# MGB-001-IO-NO-AUDIO.net
KiCad netlist of a schematic drawn in EAGLE
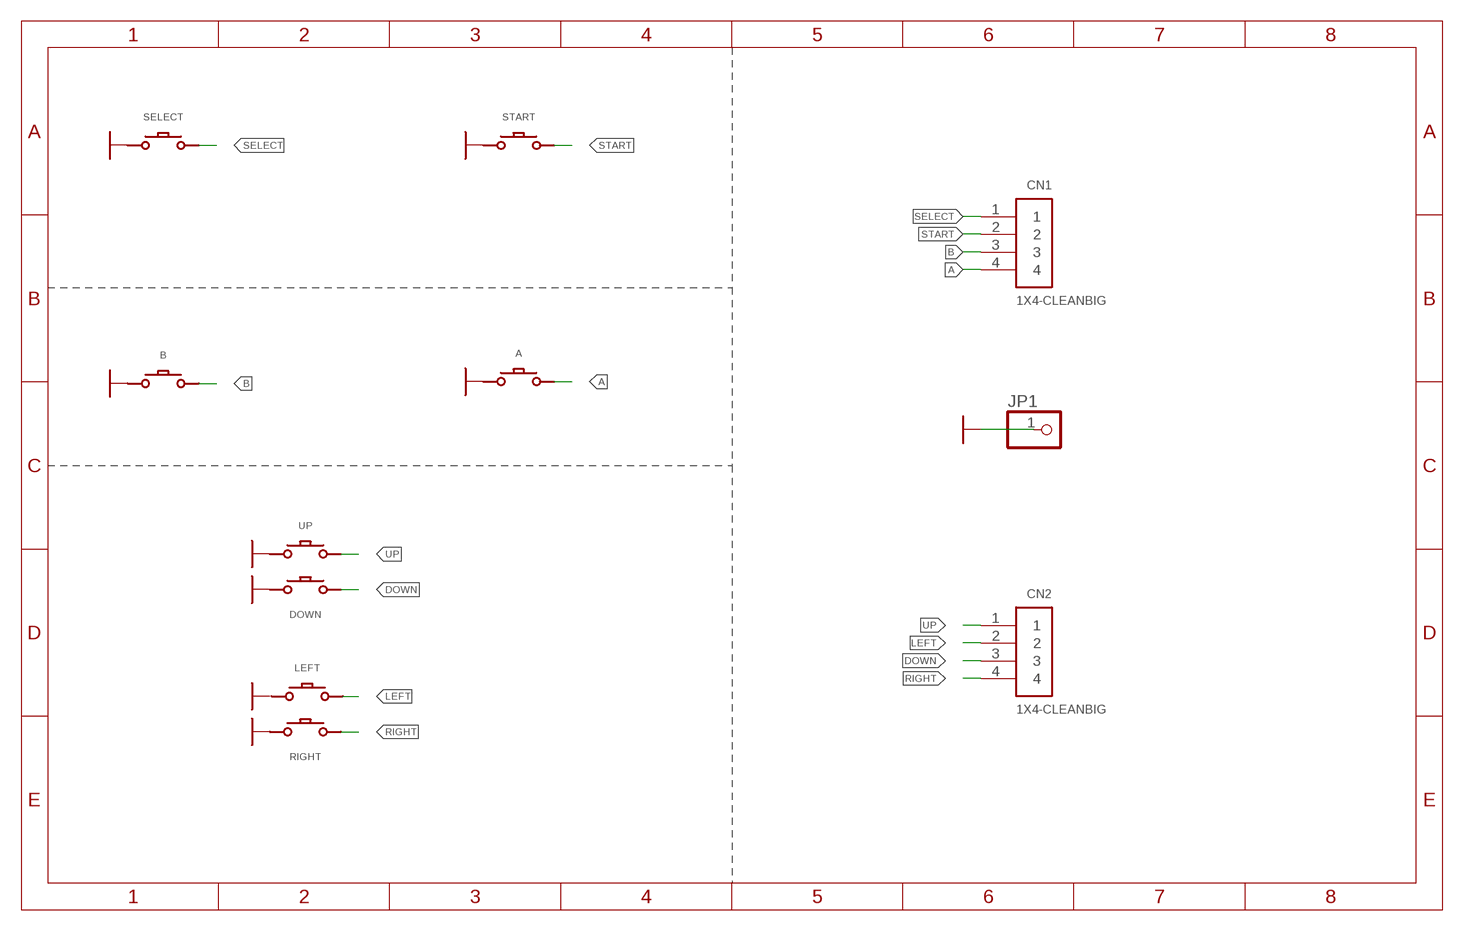
[diagram p0: schematic, sheet 1]
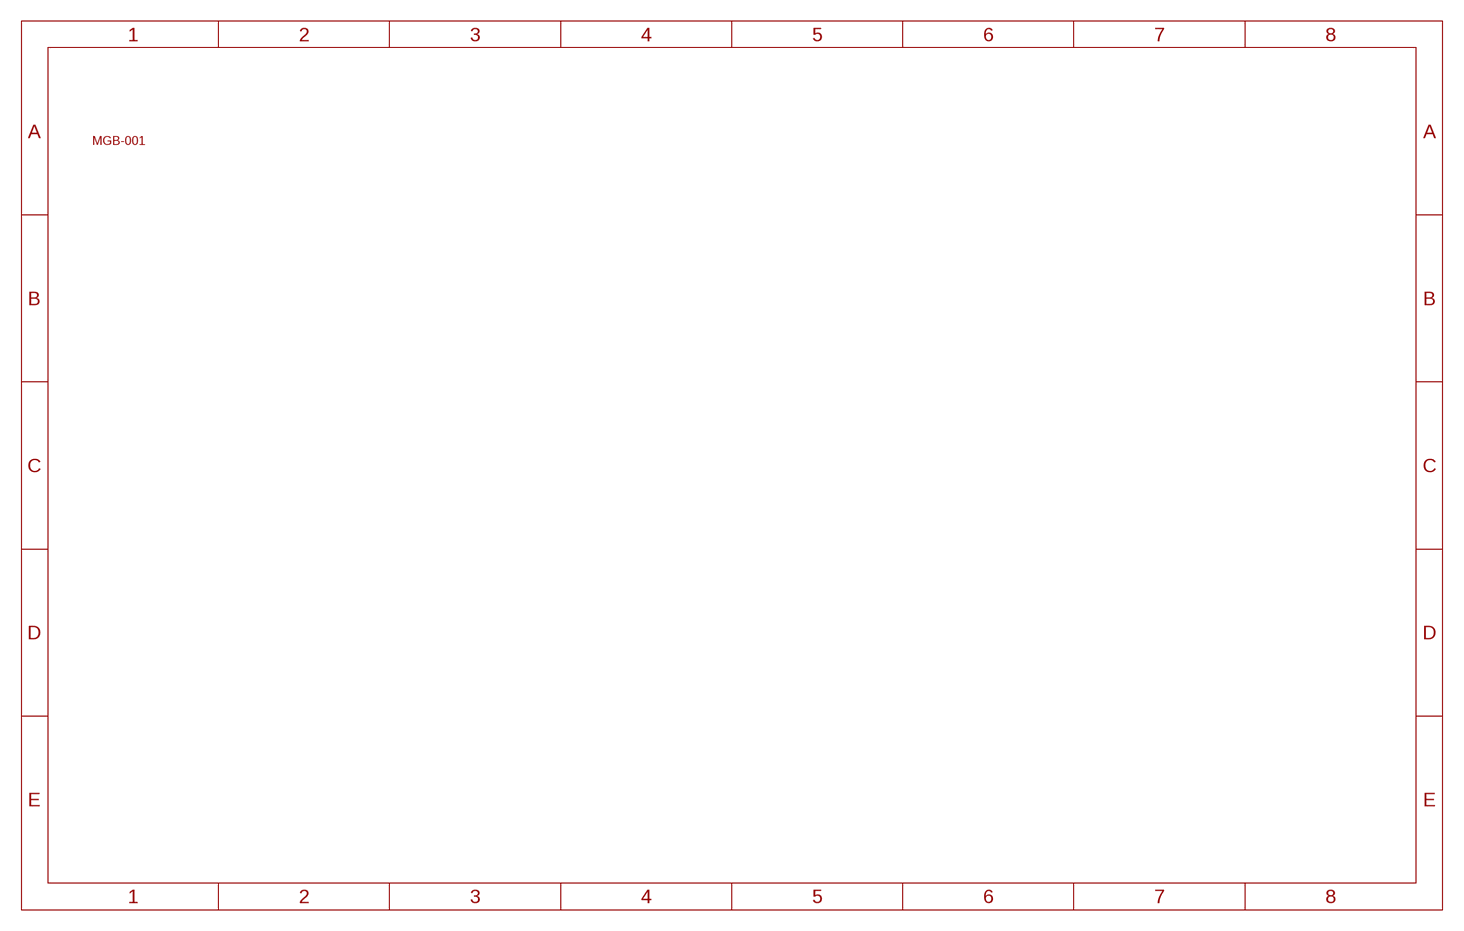
[diagram p1: schematic, sheet 2]

(export (version "E")
  (design (tool "Eeschema 10.0.6"))
  (components
    (comp (ref "U$17")
      (value "MGB-001MGB-001-IO-NO-AUDIO")
      (footprint "eagle-import:MGB-001-IO-NO-AUDIO")
      (libsource (lib "eagle-import") (part "MGB-001MGB-001-IO-NO-AUDIO"))
    )
    (comp (ref "A")
      (value "CONDUCTIVE_BUTTONCONDUCTIVE_BUTTON_THICK")
      (footprint "eagle-import:CONDUCTIVE_BUTTON_THICK")
      (libsource (lib "eagle-import") (part "CONDUCTIVE_BUTTONCONDUCTIVE_BUTTON_THICK"))
    )
    (comp (ref "B")
      (value "CONDUCTIVE_BUTTONCONDUCTIVE_BUTTON_THICK")
      (footprint "eagle-import:CONDUCTIVE_BUTTON_THICK")
      (libsource (lib "eagle-import") (part "CONDUCTIVE_BUTTONCONDUCTIVE_BUTTON_THICK"))
    )
    (comp (ref "CN1")
      (value "1X4-CLEANBIG")
      (footprint "eagle-import:1X04-CLEANBIG")
      (libsource (lib "eagle-import") (part "1X4-CLEANBIG"))
    )
    (comp (ref "CN2")
      (value "1X4-CLEANBIG")
      (footprint "eagle-import:1X04-CLEANBIG")
      (libsource (lib "eagle-import") (part "1X4-CLEANBIG"))
    )
    (comp (ref "DOWN")
      (value "CONDUCTIVE_BUTTONCONDUCTIVE_BUTTON_DIRECTIONAL_THICK")
      (footprint "eagle-import:CONDUCTIVE_BUTTON_DIRECTIONAL_THICK")
      (libsource (lib "eagle-import") (part "CONDUCTIVE_BUTTONCONDUCTIVE_BUTTON_DIRECTIONAL_THICK"))
    )
    (comp (ref "JP1")
      (value "PINHD-1X1CB")
      (footprint "eagle-import:1X01-CLEANBIG")
      (libsource (lib "eagle-import") (part "PINHD-1X1CB"))
    )
    (comp (ref "LEFT")
      (value "CONDUCTIVE_BUTTONCONDUCTIVE_BUTTON_DIRECTIONAL_THICK")
      (footprint "eagle-import:CONDUCTIVE_BUTTON_DIRECTIONAL_THICK")
      (libsource (lib "eagle-import") (part "CONDUCTIVE_BUTTONCONDUCTIVE_BUTTON_DIRECTIONAL_THICK"))
    )
    (comp (ref "RIGHT")
      (value "CONDUCTIVE_BUTTONCONDUCTIVE_BUTTON_DIRECTIONAL_THICK")
      (footprint "eagle-import:CONDUCTIVE_BUTTON_DIRECTIONAL_THICK")
      (libsource (lib "eagle-import") (part "CONDUCTIVE_BUTTONCONDUCTIVE_BUTTON_DIRECTIONAL_THICK"))
    )
    (comp (ref "SELECT")
      (value "CONDUCTIVE_BUTTON_STARTSELECTCONDUCTIVE_BUTTON_THICK_STARTSELECT")
      (footprint "eagle-import:CONDUCTIVE_BUTTON_THICK_STARTSELECT")
      (libsource (lib "eagle-import") (part "CONDUCTIVE_BUTTON_STARTSELECTCONDUCTIVE_BUTTON_THICK_STARTSELECT"))
    )
    (comp (ref "START")
      (value "CONDUCTIVE_BUTTON_STARTSELECTCONDUCTIVE_BUTTON_THICK_STARTSELECT")
      (footprint "eagle-import:CONDUCTIVE_BUTTON_THICK_STARTSELECT")
      (libsource (lib "eagle-import") (part "CONDUCTIVE_BUTTON_STARTSELECTCONDUCTIVE_BUTTON_THICK_STARTSELECT"))
    )
    (comp (ref "UP")
      (value "CONDUCTIVE_BUTTONCONDUCTIVE_BUTTON_DIRECTIONAL_THICK")
      (footprint "eagle-import:CONDUCTIVE_BUTTON_DIRECTIONAL_THICK")
      (libsource (lib "eagle-import") (part "CONDUCTIVE_BUTTONCONDUCTIVE_BUTTON_DIRECTIONAL_THICK"))
    )
  )
  (nets
    (net (code "1") (name "A") (class "Default")
      (node (ref "A") (pin "P$ACTIVE") (pinfunction "P$ACTIVE_P$ACTIVE") (pintype "bidirectional"))
      (node (ref "CN1") (pin "4") (pinfunction "4_4") (pintype "bidirectional"))
    )
    (net (code "2") (name "B") (class "Default")
      (node (ref "B") (pin "P$ACTIVE") (pinfunction "P$ACTIVE_P$ACTIVE") (pintype "bidirectional"))
      (node (ref "CN1") (pin "3") (pinfunction "3_3") (pintype "bidirectional"))
    )
    (net (code "3") (name "DOWN") (class "Default")
      (node (ref "CN2") (pin "3") (pinfunction "3_3") (pintype "bidirectional"))
      (node (ref "DOWN") (pin "P$ACTIVE") (pinfunction "P$ACTIVE_P$ACTIVE") (pintype "bidirectional"))
    )
    (net (code "4") (name "GND") (class "Default")
      (node (ref "A") (pin "P$GND") (pinfunction "P$GND_P$GND") (pintype "bidirectional"))
      (node (ref "B") (pin "P$GND") (pinfunction "P$GND_P$GND") (pintype "bidirectional"))
      (node (ref "DOWN") (pin "P$GND") (pinfunction "P$GND_P$GND") (pintype "bidirectional"))
      (node (ref "JP1") (pin "1") (pinfunction "1_1") (pintype "passive"))
      (node (ref "RIGHT") (pin "P$GND") (pinfunction "P$GND_P$GND") (pintype "bidirectional"))
      (node (ref "SELECT") (pin "P$GND") (pinfunction "P$GND_P$GND") (pintype "bidirectional"))
      (node (ref "SELECT") (pin "P$GND1") (pinfunction "P$GND_P$GND1") (pintype "bidirectional"))
      (node (ref "SELECT") (pin "P$GND2") (pinfunction "P$GND_P$GND2") (pintype "bidirectional"))
      (node (ref "SELECT") (pin "P$GND3") (pinfunction "P$GND_P$GND3") (pintype "bidirectional"))
      (node (ref "START") (pin "P$GND") (pinfunction "P$GND_P$GND") (pintype "bidirectional"))
      (node (ref "START") (pin "P$GND1") (pinfunction "P$GND_P$GND1") (pintype "bidirectional"))
      (node (ref "START") (pin "P$GND2") (pinfunction "P$GND_P$GND2") (pintype "bidirectional"))
      (node (ref "START") (pin "P$GND3") (pinfunction "P$GND_P$GND3") (pintype "bidirectional"))
      (node (ref "UP") (pin "P$GND") (pinfunction "P$GND_P$GND") (pintype "bidirectional"))
    )
    (net (code "5") (name "LEFT") (class "Default")
      (node (ref "CN2") (pin "2") (pinfunction "2_2") (pintype "bidirectional"))
      (node (ref "LEFT") (pin "P$ACTIVE") (pinfunction "P$ACTIVE_P$ACTIVE") (pintype "bidirectional"))
    )
    (net (code "6") (name "RIGHT") (class "Default")
      (node (ref "CN2") (pin "4") (pinfunction "4_4") (pintype "bidirectional"))
      (node (ref "RIGHT") (pin "P$ACTIVE") (pinfunction "P$ACTIVE_P$ACTIVE") (pintype "bidirectional"))
    )
    (net (code "7") (name "SELECT") (class "Default")
      (node (ref "CN1") (pin "1") (pinfunction "1_1") (pintype "bidirectional"))
      (node (ref "SELECT") (pin "P$ACTIVE") (pinfunction "P$ACTIVE_P$ACTIVE") (pintype "bidirectional"))
      (node (ref "SELECT") (pin "P$ACTIVE1") (pinfunction "P$ACTIVE_P$ACTIVE1") (pintype "bidirectional"))
      (node (ref "SELECT") (pin "P$ACTIVE2") (pinfunction "P$ACTIVE_P$ACTIVE2") (pintype "bidirectional"))
      (node (ref "SELECT") (pin "P$ACTIVE3") (pinfunction "P$ACTIVE_P$ACTIVE3") (pintype "bidirectional"))
      (node (ref "SELECT") (pin "P$ACTIVE4") (pinfunction "P$ACTIVE_P$ACTIVE4") (pintype "bidirectional"))
      (node (ref "SELECT") (pin "P$ACTIVE5") (pinfunction "P$ACTIVE_P$ACTIVE5") (pintype "bidirectional"))
      (node (ref "SELECT") (pin "P$ACTIVE6") (pinfunction "P$ACTIVE_P$ACTIVE6") (pintype "bidirectional"))
    )
    (net (code "8") (name "START") (class "Default")
      (node (ref "CN1") (pin "2") (pinfunction "2_2") (pintype "bidirectional"))
      (node (ref "START") (pin "P$ACTIVE") (pinfunction "P$ACTIVE_P$ACTIVE") (pintype "bidirectional"))
      (node (ref "START") (pin "P$ACTIVE1") (pinfunction "P$ACTIVE_P$ACTIVE1") (pintype "bidirectional"))
      (node (ref "START") (pin "P$ACTIVE2") (pinfunction "P$ACTIVE_P$ACTIVE2") (pintype "bidirectional"))
      (node (ref "START") (pin "P$ACTIVE3") (pinfunction "P$ACTIVE_P$ACTIVE3") (pintype "bidirectional"))
      (node (ref "START") (pin "P$ACTIVE4") (pinfunction "P$ACTIVE_P$ACTIVE4") (pintype "bidirectional"))
      (node (ref "START") (pin "P$ACTIVE5") (pinfunction "P$ACTIVE_P$ACTIVE5") (pintype "bidirectional"))
      (node (ref "START") (pin "P$ACTIVE6") (pinfunction "P$ACTIVE_P$ACTIVE6") (pintype "bidirectional"))
    )
    (net (code "9") (name "UP") (class "Default")
      (node (ref "CN2") (pin "1") (pinfunction "1_1") (pintype "bidirectional"))
      (node (ref "UP") (pin "P$ACTIVE") (pinfunction "P$ACTIVE_P$ACTIVE") (pintype "bidirectional"))
    )
    (net (code "10") (name "unconnected-(LEFT-PadP$GND)") (class "Default")
      (node (ref "LEFT") (pin "P$GND") (pinfunction "P$GND_P$GND") (pintype "bidirectional"))
    )
  )
)
